# BQ34z100pwr.net
KiCad netlist of a schematic drawn in Altium Designer
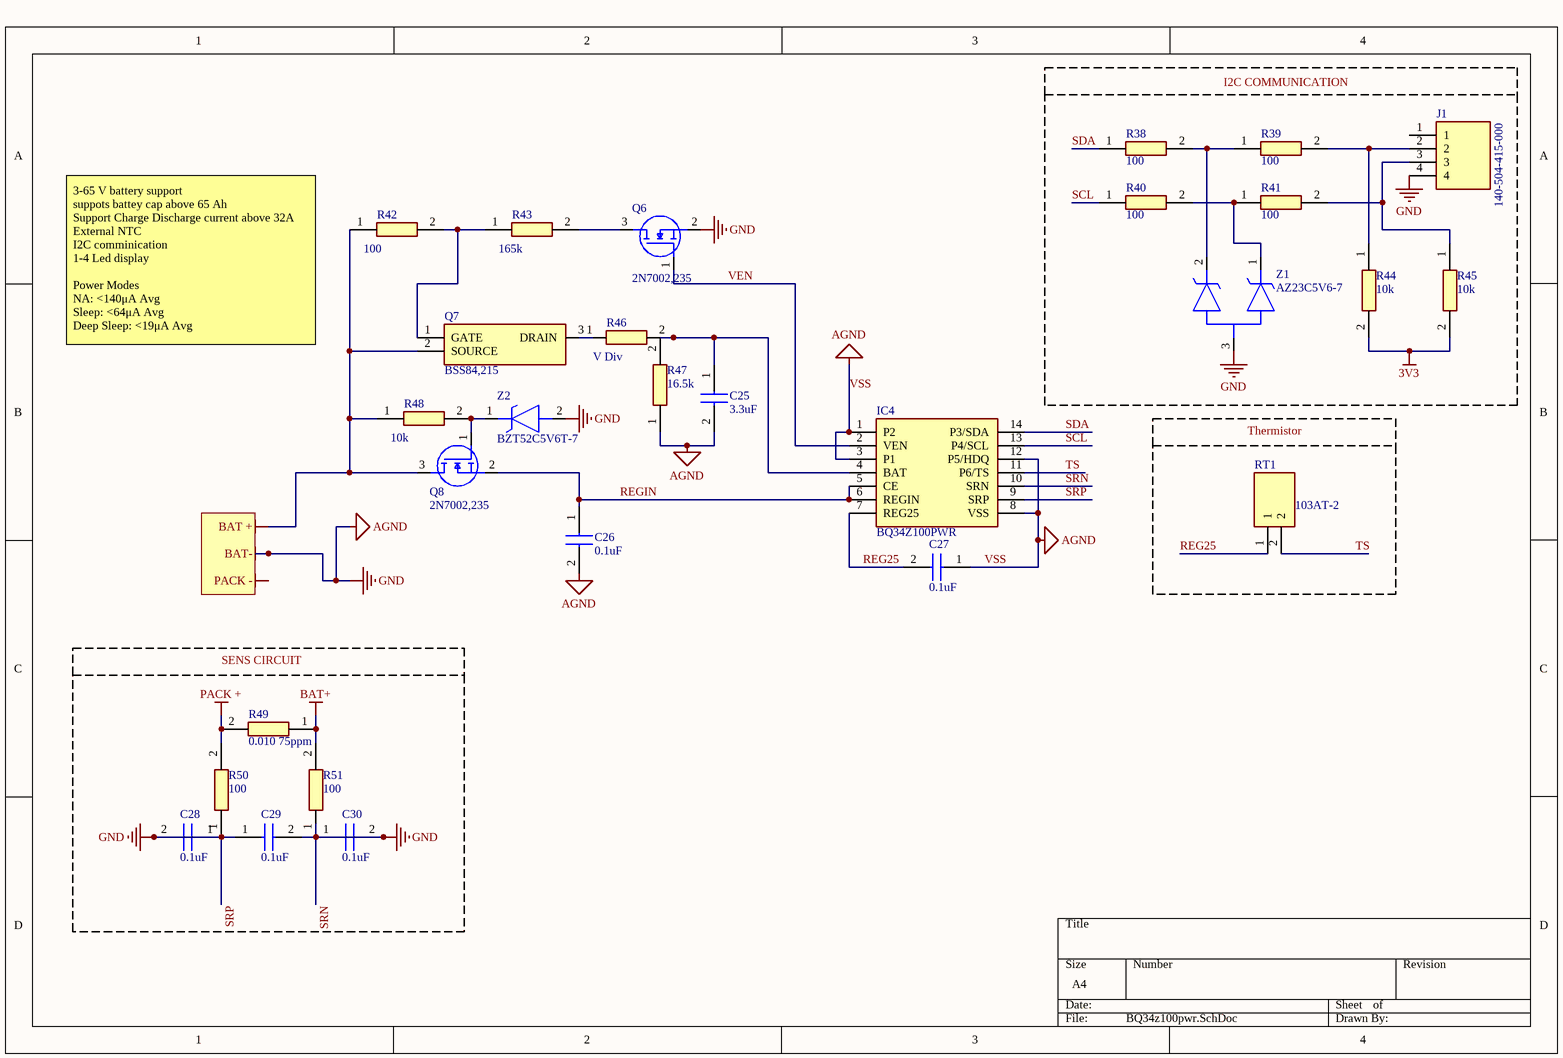
[diagram p0: BQ34z100pwr.SchDoc]

(export (version "E")
  (design (tool "Eeschema 10.0.6"))
  (components
    (comp (ref "C25")
      (value "3.3uF")
      (footprint "SamacSys:CAPC1608X90N")
      (description "Capacitor")
      (fields
        (field (name "MANUFACTURER_PART_NUMBER") "EMK107B7104KAHT")
        (field (name "MOUSER PART NUMBER") "963-EMK107B7104KAHT")
      )
      (libsource (lib "*") (part "EMK107B7104KAHT"))
    )
    (comp (ref "C26")
      (value "0.1uF")
      (footprint "SamacSys:CAPC1608X90N")
      (description "Capacitor")
      (fields
        (field (name "MANUFACTURER_PART_NUMBER") "EMK107B7104KAHT")
        (field (name "MOUSER PART NUMBER") "963-EMK107B7104KAHT")
      )
      (libsource (lib "*") (part "EMK107B7104KAHT"))
    )
    (comp (ref "C27")
      (value "0.1uF")
      (footprint "SamacSys:CAPC1608X90N")
      (description "Capacitor")
      (fields
        (field (name "MANUFACTURER_PART_NUMBER") "EMK107B7104KAHT")
        (field (name "MOUSER PART NUMBER") "963-EMK107B7104KAHT")
      )
      (libsource (lib "*") (part "EMK107B7104KAHT"))
    )
    (comp (ref "C28")
      (value "0.1uF")
      (footprint "SamacSys:CAPC1608X90N")
      (description "Capacitor")
      (fields
        (field (name "MANUFACTURER_PART_NUMBER") "EMK107B7104KAHT")
        (field (name "MOUSER PART NUMBER") "963-EMK107B7104KAHT")
      )
      (libsource (lib "*") (part "EMK107B7104KAHT"))
    )
    (comp (ref "C29")
      (value "0.1uF")
      (footprint "SamacSys:CAPC1608X90N")
      (description "Capacitor")
      (fields
        (field (name "MANUFACTURER_PART_NUMBER") "EMK107B7104KAHT")
        (field (name "MOUSER PART NUMBER") "963-EMK107B7104KAHT")
      )
      (libsource (lib "*") (part "EMK107B7104KAHT"))
    )
    (comp (ref "C30")
      (value "0.1uF")
      (footprint "SamacSys:CAPC1608X90N")
      (description "Capacitor")
      (fields
        (field (name "MANUFACTURER_PART_NUMBER") "EMK107B7104KAHT")
        (field (name "MOUSER PART NUMBER") "963-EMK107B7104KAHT")
      )
      (libsource (lib "*") (part "EMK107B7104KAHT"))
    )
    (comp (ref "IC4")
      (value "BQ34Z100PWR")
      (footprint "SOP65P640X120-14N")
      (description "Integrated Circuit")
      (fields (field (name "MOUSER PART NUMBER") "595-BQ34Z100PWR"))
      (libsource (lib "Schlib1") (part "BQ34Z100PWR"))
    )
    (comp (ref "J1")
      (value "140-504-415-000")
      (footprint "SamacSys:140504415000")
      (description "Connector")
      (fields (field (name "MOUSER PART NUMBER") "587-140-504-415-000"))
      (libsource (lib "*") (part "140-504-415-000"))
    )
    (comp (ref "Q6")
      (value "2N7002,235")
      (footprint "SamacSys:SOT95P230X110-3N")
      (description "MOSFET (N-Channel)")
      (fields (field (name "MOUSER PART NUMBER") "771-2N7002235"))
      (libsource (lib "Schlib1") (part "2N7002,235"))
    )
    (comp (ref "Q7")
      (value "BSS84,215")
      (footprint "SamacSys:SOT95P230X110-3N")
      (description "Transistor")
      (fields (field (name "MOUSER PART NUMBER") "771-BSS84-T/R"))
      (libsource (lib "Schlib1") (part "BSS84,215"))
    )
    (comp (ref "Q8")
      (value "2N7002,235")
      (footprint "SamacSys:SOT95P230X110-3N")
      (description "MOSFET (N-Channel)")
      (fields (field (name "MOUSER PART NUMBER") "771-2N7002235"))
      (libsource (lib "*") (part "2N7002,235"))
    )
    (comp (ref "R38")
      (value "100")
      (footprint "SamacSys:RESC1608X55N")
      (description "Resistor")
      (fields
        (field (name "MANUFACTURER_PART_NUMBER") "CR0603-FX-1003ELF")
        (field (name "MOUSER PART NUMBER") "652-CR0603-FX-103ELF")
      )
      (libsource (lib "Schlib1") (part "CR0603-FX-1003ELF"))
    )
    (comp (ref "R39")
      (value "100")
      (footprint "SamacSys:RESC1608X55N")
      (description "Resistor")
      (fields
        (field (name "MANUFACTURER_PART_NUMBER") "CR0603-FX-1003ELF")
        (field (name "MOUSER PART NUMBER") "652-CR0603-FX-103ELF")
      )
      (libsource (lib "Schlib1") (part "CR0603-FX-1003ELF"))
    )
    (comp (ref "R40")
      (value "100")
      (footprint "SamacSys:RESC1608X55N")
      (description "Resistor")
      (fields
        (field (name "MANUFACTURER_PART_NUMBER") "CR0603-FX-1003ELF")
        (field (name "MOUSER PART NUMBER") "652-CR0603-FX-103ELF")
      )
      (libsource (lib "Schlib1") (part "CR0603-FX-1003ELF"))
    )
    (comp (ref "R41")
      (value "100")
      (footprint "SamacSys:RESC1608X55N")
      (description "Resistor")
      (fields
        (field (name "MANUFACTURER_PART_NUMBER") "CR0603-FX-1003ELF")
        (field (name "MOUSER PART NUMBER") "652-CR0603-FX-103ELF")
      )
      (libsource (lib "Schlib1") (part "CR0603-FX-1003ELF"))
    )
    (comp (ref "R42")
      (value "100")
      (footprint "SamacSys:RESC1608X55N")
      (description "Resistor")
      (fields
        (field (name "MANUFACTURER_PART_NUMBER") "CR0603-FX-1003ELF")
        (field (name "MOUSER PART NUMBER") "652-CR0603-FX-103ELF")
      )
      (libsource (lib "Schlib1") (part "CR0603-FX-1003ELF"))
    )
    (comp (ref "R43")
      (value "165k")
      (footprint "SamacSys:RESC1608X55N")
      (description "Resistor")
      (fields
        (field (name "MANUFACTURER_PART_NUMBER") "CR0603-FX-1003ELF")
        (field (name "MOUSER PART NUMBER") "652-CR0603-FX-103ELF")
      )
      (libsource (lib "Schlib1") (part "CR0603-FX-1003ELF"))
    )
    (comp (ref "R44")
      (value "10k")
      (footprint "SamacSys:RESC1608X55N")
      (description "Resistor")
      (fields
        (field (name "MANUFACTURER_PART_NUMBER") "CR0603-FX-1003ELF")
        (field (name "MOUSER PART NUMBER") "652-CR0603-FX-103ELF")
      )
      (libsource (lib "") (part "CR0603-FX-1003ELF_1"))
    )
    (comp (ref "R45")
      (value "10k")
      (footprint "SamacSys:RESC1608X55N")
      (description "Resistor")
      (fields
        (field (name "MANUFACTURER_PART_NUMBER") "CR0603-FX-1003ELF")
        (field (name "MOUSER PART NUMBER") "652-CR0603-FX-103ELF")
      )
      (libsource (lib "") (part "CR0603-FX-1003ELF_1"))
    )
    (comp (ref "R46")
      (value "V Div")
      (footprint "SamacSys:RESC1608X55N")
      (description "Resistor")
      (fields
        (field (name "MANUFACTURER_PART_NUMBER") "CR0603-FX-1003ELF")
        (field (name "MOUSER PART NUMBER") "652-CR0603-FX-103ELF")
      )
      (libsource (lib "Schlib1") (part "CR0603-FX-1003ELF"))
    )
    (comp (ref "R47")
      (value "16.5k")
      (footprint "SamacSys:RESC1608X55N")
      (description "Resistor")
      (fields
        (field (name "MANUFACTURER_PART_NUMBER") "CR0603-FX-1003ELF")
        (field (name "MOUSER PART NUMBER") "652-CR0603-FX-103ELF")
      )
      (libsource (lib "") (part "CR0603-FX-1003ELF_2"))
    )
    (comp (ref "R48")
      (value "10k")
      (footprint "SamacSys:RESC1608X55N")
      (description "Resistor")
      (fields
        (field (name "MANUFACTURER_PART_NUMBER") "CR0603-FX-1003ELF")
        (field (name "MOUSER PART NUMBER") "652-CR0603-FX-103ELF")
      )
      (libsource (lib "Schlib1") (part "CR0603-FX-1003ELF"))
    )
    (comp (ref "R49")
      (value "0.010 75ppm")
      (footprint "SamacSys:RESC1608X55N")
      (description "Resistor")
      (fields
        (field (name "MANUFACTURER_PART_NUMBER") "CR0603-FX-1003ELF")
        (field (name "MOUSER PART NUMBER") "652-CR0603-FX-103ELF")
      )
      (libsource (lib "") (part "CR0603-FX-1003ELF_3"))
    )
    (comp (ref "R50")
      (value "100")
      (footprint "SamacSys:RESC1608X55N")
      (description "Resistor")
      (fields
        (field (name "MANUFACTURER_PART_NUMBER") "CR0603-FX-1003ELF")
        (field (name "MOUSER PART NUMBER") "652-CR0603-FX-103ELF")
      )
      (libsource (lib "") (part "CR0603-FX-1003ELF_2"))
    )
    (comp (ref "R51")
      (value "100")
      (footprint "SamacSys:RESC1608X55N")
      (description "Resistor")
      (fields
        (field (name "MANUFACTURER_PART_NUMBER") "CR0603-FX-1003ELF")
        (field (name "MOUSER PART NUMBER") "652-CR0603-FX-103ELF")
      )
      (libsource (lib "") (part "CR0603-FX-1003ELF_2"))
    )
    (comp (ref "RT1")
      (value "103AT-2")
      (footprint "PcbLib1:103AT2")
      (description "Thermistor")
      (fields (field (name "MOUSER PART NUMBER") "954-103AT-2"))
      (libsource (lib "Schlib1") (part "103AT-2"))
    )
    (comp (ref "Z1")
      (value "AZ23C5V6-7")
      (footprint "SamacSys:SOT96P240X110-3N")
      (description "Zener Diode")
      (fields (field (name "MOUSER PART NUMBER") "621-AZ23C5V6"))
      (libsource (lib "*") (part "AZ23C5V6-7"))
    )
    (comp (ref "Z2")
      (value "BZT52C5V6T-7")
      (footprint "SamacSys:SODFL1608X65N")
      (description "Zener Diode")
      (fields (field (name "MOUSER PART NUMBER") "621-BZT52C5V6T-7"))
      (libsource (lib "Schlib1") (part "BZT52C5V6T-7"))
    )
  )
  (nets
    (net (code "1") (name "/REG25") (class "Default")
      (node (ref "C27") (pin "2") (pinfunction "2_2") (pintype "passive"))
      (node (ref "IC4") (pin "7") (pinfunction "REG25_7") (pintype "passive"))
      (node (ref "RT1") (pin "1") (pinfunction "1_1") (pintype "passive"))
    )
    (net (code "2") (name "/REGIN") (class "Default")
      (node (ref "C26") (pin "1") (pinfunction "1_1") (pintype "passive"))
      (node (ref "IC4") (pin "5") (pinfunction "CE_5") (pintype "passive"))
      (node (ref "IC4") (pin "6") (pinfunction "REGIN_6") (pintype "passive"))
      (node (ref "Q8") (pin "2") (pinfunction "S_2") (pintype "passive"))
    )
    (net (code "3") (name "/SCL") (class "Default")
      (node (ref "IC4") (pin "13") (pinfunction "P4/SCL_13") (pintype "passive"))
      (node (ref "R40") (pin "1") (pinfunction "1_1") (pintype "passive"))
    )
    (net (code "4") (name "/SDA") (class "Default")
      (node (ref "IC4") (pin "14") (pinfunction "P3/SDA_14") (pintype "passive"))
      (node (ref "R38") (pin "1") (pinfunction "1_1") (pintype "passive"))
    )
    (net (code "5") (name "/TS") (class "Default")
      (node (ref "IC4") (pin "11") (pinfunction "P6/TS_11") (pintype "passive"))
      (node (ref "RT1") (pin "2") (pinfunction "2_2") (pintype "passive"))
    )
    (net (code "6") (name "/VEN") (class "Default")
      (node (ref "IC4") (pin "2") (pinfunction "VEN_2") (pintype "passive"))
      (node (ref "Q6") (pin "1") (pinfunction "G_1") (pintype "passive"))
    )
    (net (code "7") (name "3V3") (class "Default")
      (node (ref "R44") (pin "2") (pinfunction "2_2") (pintype "passive"))
      (node (ref "R45") (pin "2") (pinfunction "2_2") (pintype "passive"))
    )
    (net (code "8") (name "AGND") (class "Default")
      (node (ref "C25") (pin "2") (pinfunction "2_2") (pintype "passive"))
      (node (ref "C26") (pin "2") (pinfunction "2_2") (pintype "passive"))
      (node (ref "C27") (pin "1") (pinfunction "1_1") (pintype "passive"))
      (node (ref "C28") (pin "1") (pinfunction "1_1") (pintype "passive"))
      (node (ref "C28") (pin "2") (pinfunction "2_2") (pintype "passive"))
      (node (ref "C29") (pin "1") (pinfunction "1_1") (pintype "passive"))
      (node (ref "C29") (pin "2") (pinfunction "2_2") (pintype "passive"))
      (node (ref "C30") (pin "1") (pinfunction "1_1") (pintype "passive"))
      (node (ref "C30") (pin "2") (pinfunction "2_2") (pintype "passive"))
      (node (ref "IC4") (pin "1") (pinfunction "P2_1") (pintype "passive"))
      (node (ref "IC4") (pin "10") (pinfunction "SRN_10") (pintype "passive"))
      (node (ref "IC4") (pin "12") (pinfunction "P5/HDQ_12") (pintype "passive"))
      (node (ref "IC4") (pin "3") (pinfunction "P1_3") (pintype "passive"))
      (node (ref "IC4") (pin "8") (pinfunction "VSS_8") (pintype "passive"))
      (node (ref "IC4") (pin "9") (pinfunction "SRP_9") (pintype "passive"))
      (node (ref "J1") (pin "4") (pinfunction "4_4") (pintype "passive"))
      (node (ref "Q6") (pin "2") (pinfunction "S_2") (pintype "passive"))
      (node (ref "R47") (pin "1") (pinfunction "1_1") (pintype "passive"))
      (node (ref "R50") (pin "1") (pinfunction "1_1") (pintype "passive"))
      (node (ref "R51") (pin "1") (pinfunction "1_1") (pintype "passive"))
      (node (ref "Z1") (pin "3") (pinfunction "COMMON_ANODE_3") (pintype "passive"))
      (node (ref "Z2") (pin "2") (pinfunction "A_2") (pintype "passive"))
    )
    (net (code "9") (name "BAT +") (class "Default")
      (node (ref "Q7") (pin "2") (pinfunction "SOURCE_2") (pintype "passive"))
      (node (ref "Q8") (pin "3") (pinfunction "D_3") (pintype "passive"))
      (node (ref "R42") (pin "1") (pinfunction "1_1") (pintype "passive"))
      (node (ref "R48") (pin "1") (pinfunction "1_1") (pintype "passive"))
    )
    (net (code "10") (name "BAT+") (class "Default")
      (node (ref "R49") (pin "1") (pinfunction "1_1") (pintype "passive"))
      (node (ref "R51") (pin "2") (pinfunction "2_2") (pintype "passive"))
    )
    (net (code "11") (name "Net-(IC4-BAT)") (class "Default")
      (node (ref "C25") (pin "1") (pinfunction "1_1") (pintype "passive"))
      (node (ref "IC4") (pin "4") (pinfunction "BAT_4") (pintype "passive"))
      (node (ref "R46") (pin "2") (pinfunction "2_2") (pintype "passive"))
      (node (ref "R47") (pin "2") (pinfunction "2_2") (pintype "passive"))
    )
    (net (code "12") (name "Net-(J1-Pad2)") (class "Default")
      (node (ref "J1") (pin "2") (pinfunction "2_2") (pintype "passive"))
      (node (ref "R39") (pin "2") (pinfunction "2_2") (pintype "passive"))
      (node (ref "R44") (pin "1") (pinfunction "1_1") (pintype "passive"))
    )
    (net (code "13") (name "Net-(J1-Pad3)") (class "Default")
      (node (ref "J1") (pin "3") (pinfunction "3_3") (pintype "passive"))
      (node (ref "R41") (pin "2") (pinfunction "2_2") (pintype "passive"))
      (node (ref "R45") (pin "1") (pinfunction "1_1") (pintype "passive"))
    )
    (net (code "14") (name "Net-(Q6-D)") (class "Default")
      (node (ref "Q6") (pin "3") (pinfunction "D_3") (pintype "passive"))
      (node (ref "R43") (pin "2") (pinfunction "2_2") (pintype "passive"))
    )
    (net (code "15") (name "Net-(Q7-DRAIN)") (class "Default")
      (node (ref "Q7") (pin "3") (pinfunction "DRAIN_3") (pintype "passive"))
      (node (ref "R46") (pin "1") (pinfunction "1_1") (pintype "passive"))
    )
    (net (code "16") (name "Net-(Q7-GATE)") (class "Default")
      (node (ref "Q7") (pin "1") (pinfunction "GATE_1") (pintype "passive"))
      (node (ref "R42") (pin "2") (pinfunction "2_2") (pintype "passive"))
      (node (ref "R43") (pin "1") (pinfunction "1_1") (pintype "passive"))
    )
    (net (code "17") (name "Net-(Q8-G)") (class "Default")
      (node (ref "Q8") (pin "1") (pinfunction "G_1") (pintype "passive"))
      (node (ref "R48") (pin "2") (pinfunction "2_2") (pintype "passive"))
      (node (ref "Z2") (pin "1") (pinfunction "K_1") (pintype "passive"))
    )
    (net (code "18") (name "Net-(Z1-CATHODE_1)") (class "Default")
      (node (ref "R40") (pin "2") (pinfunction "2_2") (pintype "passive"))
      (node (ref "R41") (pin "1") (pinfunction "1_1") (pintype "passive"))
      (node (ref "Z1") (pin "1") (pinfunction "CATHODE_1_1") (pintype "passive"))
    )
    (net (code "19") (name "Net-(Z1-CATHODE_2)") (class "Default")
      (node (ref "R38") (pin "2") (pinfunction "2_2") (pintype "passive"))
      (node (ref "R39") (pin "1") (pinfunction "1_1") (pintype "passive"))
      (node (ref "Z1") (pin "2") (pinfunction "CATHODE_2_2") (pintype "passive"))
    )
    (net (code "20") (name "PACK +") (class "Default")
      (node (ref "R49") (pin "2") (pinfunction "2_2") (pintype "passive"))
      (node (ref "R50") (pin "2") (pinfunction "2_2") (pintype "passive"))
    )
    (net (code "22") (name "unconnected-(J1-Pad1)") (class "Default")
      (node (ref "J1") (pin "1") (pinfunction "1_1") (pintype "passive"))
    )
  )
)
